# testboard.net
KiCad netlist of a schematic drawn in EAGLE
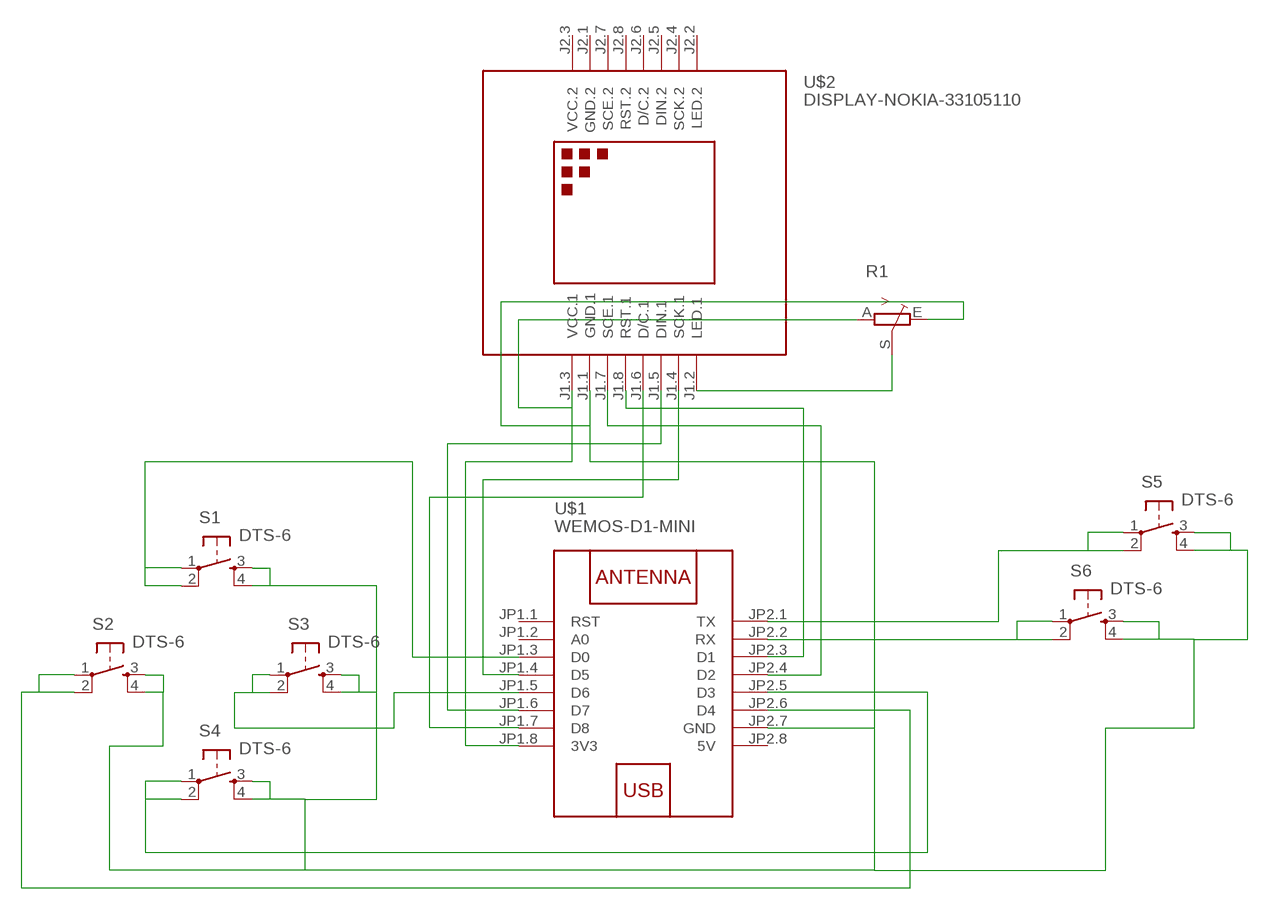
[diagram p0: schematic, sheet 1]

(export (version "E")
  (design (tool "Eeschema 10.0.6"))
  (components
    (comp (ref "R1")
      (value "TRIM_EU-B25U")
      (footprint "eagle-import:B25U")
      (libsource (lib "eagle-import") (part "TRIM_EU-B25U"))
    )
    (comp (ref "S1")
      (value "DTS-6")
      (footprint "eagle-import:DTS-6")
      (libsource (lib "eagle-import") (part "DTS-6"))
    )
    (comp (ref "S2")
      (value "DTS-6")
      (footprint "eagle-import:DTS-6")
      (libsource (lib "eagle-import") (part "DTS-6"))
    )
    (comp (ref "S3")
      (value "DTS-6")
      (footprint "eagle-import:DTS-6")
      (libsource (lib "eagle-import") (part "DTS-6"))
    )
    (comp (ref "S4")
      (value "DTS-6")
      (footprint "eagle-import:DTS-6")
      (libsource (lib "eagle-import") (part "DTS-6"))
    )
    (comp (ref "S5")
      (value "DTS-6")
      (footprint "eagle-import:DTS-6")
      (libsource (lib "eagle-import") (part "DTS-6"))
    )
    (comp (ref "S6")
      (value "DTS-6")
      (footprint "eagle-import:DTS-6")
      (libsource (lib "eagle-import") (part "DTS-6"))
    )
    (comp (ref "U$1")
      (value "WEMOS-D1-MINI")
      (footprint "eagle-import:WEMOS-D1-MINI")
      (libsource (lib "eagle-import") (part "WEMOS-D1-MINI"))
    )
    (comp (ref "U$2")
      (value "DISPLAY-NOKIA-33105110")
      (footprint "eagle-import:DISPLAY-NOKIA-3310")
      (libsource (lib "eagle-import") (part "DISPLAY-NOKIA-33105110"))
    )
  )
  (nets
    (net (code "1") (name "/5V") (class "Default")
      (node (ref "U$1") (pin "JP2.8") (pinfunction "5V_JP2.8") (pintype "power_in"))
    )
    (net (code "2") (name "/GND.2") (class "Default")
      (node (ref "U$2") (pin "J2.1") (pinfunction "GND.2_J2.1") (pintype "power_in"))
    )
    (net (code "3") (name "/VCC.2") (class "Default")
      (node (ref "U$2") (pin "J2.3") (pinfunction "VCC.2_J2.3") (pintype "power_in"))
    )
    (net (code "4") (name "Net-(U$1-3V3)") (class "Default")
      (node (ref "R1") (pin "A") (pinfunction "A_A") (pintype "passive"))
      (node (ref "U$1") (pin "JP1.8") (pinfunction "3V3_JP1.8") (pintype "power_in"))
      (node (ref "U$2") (pin "J1.3") (pinfunction "VCC.1_J1.3") (pintype "power_in"))
    )
    (net (code "5") (name "Net-(U$1-D0)") (class "Default")
      (node (ref "S1") (pin "1") (pinfunction "1_1") (pintype "passive"))
      (node (ref "S1") (pin "2") (pinfunction "2_2") (pintype "passive"))
      (node (ref "U$1") (pin "JP1.3") (pinfunction "D0_JP1.3") (pintype "bidirectional"))
    )
    (net (code "6") (name "Net-(U$1-D1)") (class "Default")
      (node (ref "U$1") (pin "JP2.3") (pinfunction "D1_JP2.3") (pintype "bidirectional"))
      (node (ref "U$2") (pin "J1.8") (pinfunction "RST.1_J1.8") (pintype "bidirectional"))
    )
    (net (code "7") (name "Net-(U$1-D2)") (class "Default")
      (node (ref "U$1") (pin "JP2.4") (pinfunction "D2_JP2.4") (pintype "bidirectional"))
      (node (ref "U$2") (pin "J1.7") (pinfunction "SCE.1_J1.7") (pintype "bidirectional"))
    )
    (net (code "8") (name "Net-(U$1-D3)") (class "Default")
      (node (ref "S4") (pin "1") (pinfunction "1_1") (pintype "passive"))
      (node (ref "S4") (pin "2") (pinfunction "2_2") (pintype "passive"))
      (node (ref "U$1") (pin "JP2.5") (pinfunction "D3_JP2.5") (pintype "bidirectional"))
    )
    (net (code "9") (name "Net-(U$1-D4)") (class "Default")
      (node (ref "S2") (pin "1") (pinfunction "1_1") (pintype "passive"))
      (node (ref "S2") (pin "2") (pinfunction "2_2") (pintype "passive"))
      (node (ref "U$1") (pin "JP2.6") (pinfunction "D4_JP2.6") (pintype "bidirectional"))
    )
    (net (code "10") (name "Net-(U$1-D5)") (class "Default")
      (node (ref "U$1") (pin "JP1.4") (pinfunction "D5_JP1.4") (pintype "bidirectional"))
      (node (ref "U$2") (pin "J1.4") (pinfunction "SCK.1_J1.4") (pintype "bidirectional"))
    )
    (net (code "11") (name "Net-(U$1-D6)") (class "Default")
      (node (ref "S3") (pin "1") (pinfunction "1_1") (pintype "passive"))
      (node (ref "S3") (pin "2") (pinfunction "2_2") (pintype "passive"))
      (node (ref "U$1") (pin "JP1.5") (pinfunction "D6_JP1.5") (pintype "bidirectional"))
    )
    (net (code "12") (name "Net-(U$1-D7)") (class "Default")
      (node (ref "U$1") (pin "JP1.6") (pinfunction "D7_JP1.6") (pintype "bidirectional"))
      (node (ref "U$2") (pin "J1.5") (pinfunction "DIN.1_J1.5") (pintype "bidirectional"))
    )
    (net (code "13") (name "Net-(U$1-D8)") (class "Default")
      (node (ref "U$1") (pin "JP1.7") (pinfunction "D8_JP1.7") (pintype "bidirectional"))
      (node (ref "U$2") (pin "J1.6") (pinfunction "D/C.1_J1.6") (pintype "bidirectional"))
    )
    (net (code "14") (name "Net-(U$1-GND)") (class "Default")
      (node (ref "R1") (pin "E") (pinfunction "E_E") (pintype "passive"))
      (node (ref "S1") (pin "3") (pinfunction "3_3") (pintype "passive"))
      (node (ref "S1") (pin "4") (pinfunction "4_4") (pintype "passive"))
      (node (ref "S2") (pin "3") (pinfunction "3_3") (pintype "passive"))
      (node (ref "S2") (pin "4") (pinfunction "4_4") (pintype "passive"))
      (node (ref "S3") (pin "3") (pinfunction "3_3") (pintype "passive"))
      (node (ref "S3") (pin "4") (pinfunction "4_4") (pintype "passive"))
      (node (ref "S4") (pin "3") (pinfunction "3_3") (pintype "passive"))
      (node (ref "S4") (pin "4") (pinfunction "4_4") (pintype "passive"))
      (node (ref "S5") (pin "3") (pinfunction "3_3") (pintype "passive"))
      (node (ref "S5") (pin "4") (pinfunction "4_4") (pintype "passive"))
      (node (ref "S6") (pin "3") (pinfunction "3_3") (pintype "passive"))
      (node (ref "S6") (pin "4") (pinfunction "4_4") (pintype "passive"))
      (node (ref "U$1") (pin "JP2.7") (pinfunction "GND_JP2.7") (pintype "power_in"))
      (node (ref "U$2") (pin "J1.1") (pinfunction "GND.1_J1.1") (pintype "power_in"))
    )
    (net (code "15") (name "Net-(U$1-RX)") (class "Default")
      (node (ref "S6") (pin "1") (pinfunction "1_1") (pintype "passive"))
      (node (ref "S6") (pin "2") (pinfunction "2_2") (pintype "passive"))
      (node (ref "U$1") (pin "JP2.2") (pinfunction "RX_JP2.2") (pintype "bidirectional"))
    )
    (net (code "16") (name "Net-(U$1-TX)") (class "Default")
      (node (ref "S5") (pin "1") (pinfunction "1_1") (pintype "passive"))
      (node (ref "S5") (pin "2") (pinfunction "2_2") (pintype "passive"))
      (node (ref "U$1") (pin "JP2.1") (pinfunction "TX_JP2.1") (pintype "bidirectional"))
    )
    (net (code "17") (name "Net-(U$2-LED.1)") (class "Default")
      (node (ref "R1") (pin "S") (pinfunction "S_S") (pintype "passive"))
      (node (ref "U$2") (pin "J1.2") (pinfunction "LED.1_J1.2") (pintype "input"))
    )
    (net (code "18") (name "unconnected-(U$1-A0-PadJP1.2)") (class "Default")
      (node (ref "U$1") (pin "JP1.2") (pinfunction "A0_JP1.2") (pintype "bidirectional"))
    )
    (net (code "19") (name "unconnected-(U$1-RST-PadJP1.1)") (class "Default")
      (node (ref "U$1") (pin "JP1.1") (pinfunction "RST_JP1.1") (pintype "bidirectional"))
    )
    (net (code "20") (name "unconnected-(U$2-DIN.2-PadJ2.5)") (class "Default")
      (node (ref "U$2") (pin "J2.5") (pinfunction "DIN.2_J2.5") (pintype "bidirectional"))
    )
    (net (code "21") (name "unconnected-(U$2-D{slash}C.2-PadJ2.6)") (class "Default")
      (node (ref "U$2") (pin "J2.6") (pinfunction "D/C.2_J2.6") (pintype "bidirectional"))
    )
    (net (code "22") (name "unconnected-(U$2-LED.2-PadJ2.2)") (class "Default")
      (node (ref "U$2") (pin "J2.2") (pinfunction "LED.2_J2.2") (pintype "input"))
    )
    (net (code "23") (name "unconnected-(U$2-RST.2-PadJ2.8)") (class "Default")
      (node (ref "U$2") (pin "J2.8") (pinfunction "RST.2_J2.8") (pintype "bidirectional"))
    )
    (net (code "24") (name "unconnected-(U$2-SCE.2-PadJ2.7)") (class "Default")
      (node (ref "U$2") (pin "J2.7") (pinfunction "SCE.2_J2.7") (pintype "bidirectional"))
    )
    (net (code "25") (name "unconnected-(U$2-SCK.2-PadJ2.4)") (class "Default")
      (node (ref "U$2") (pin "J2.4") (pinfunction "SCK.2_J2.4") (pintype "bidirectional"))
    )
  )
)
